# 09_MIPI_LCD_TX1.net
KiCad netlist of a schematic drawn in Altium Designer
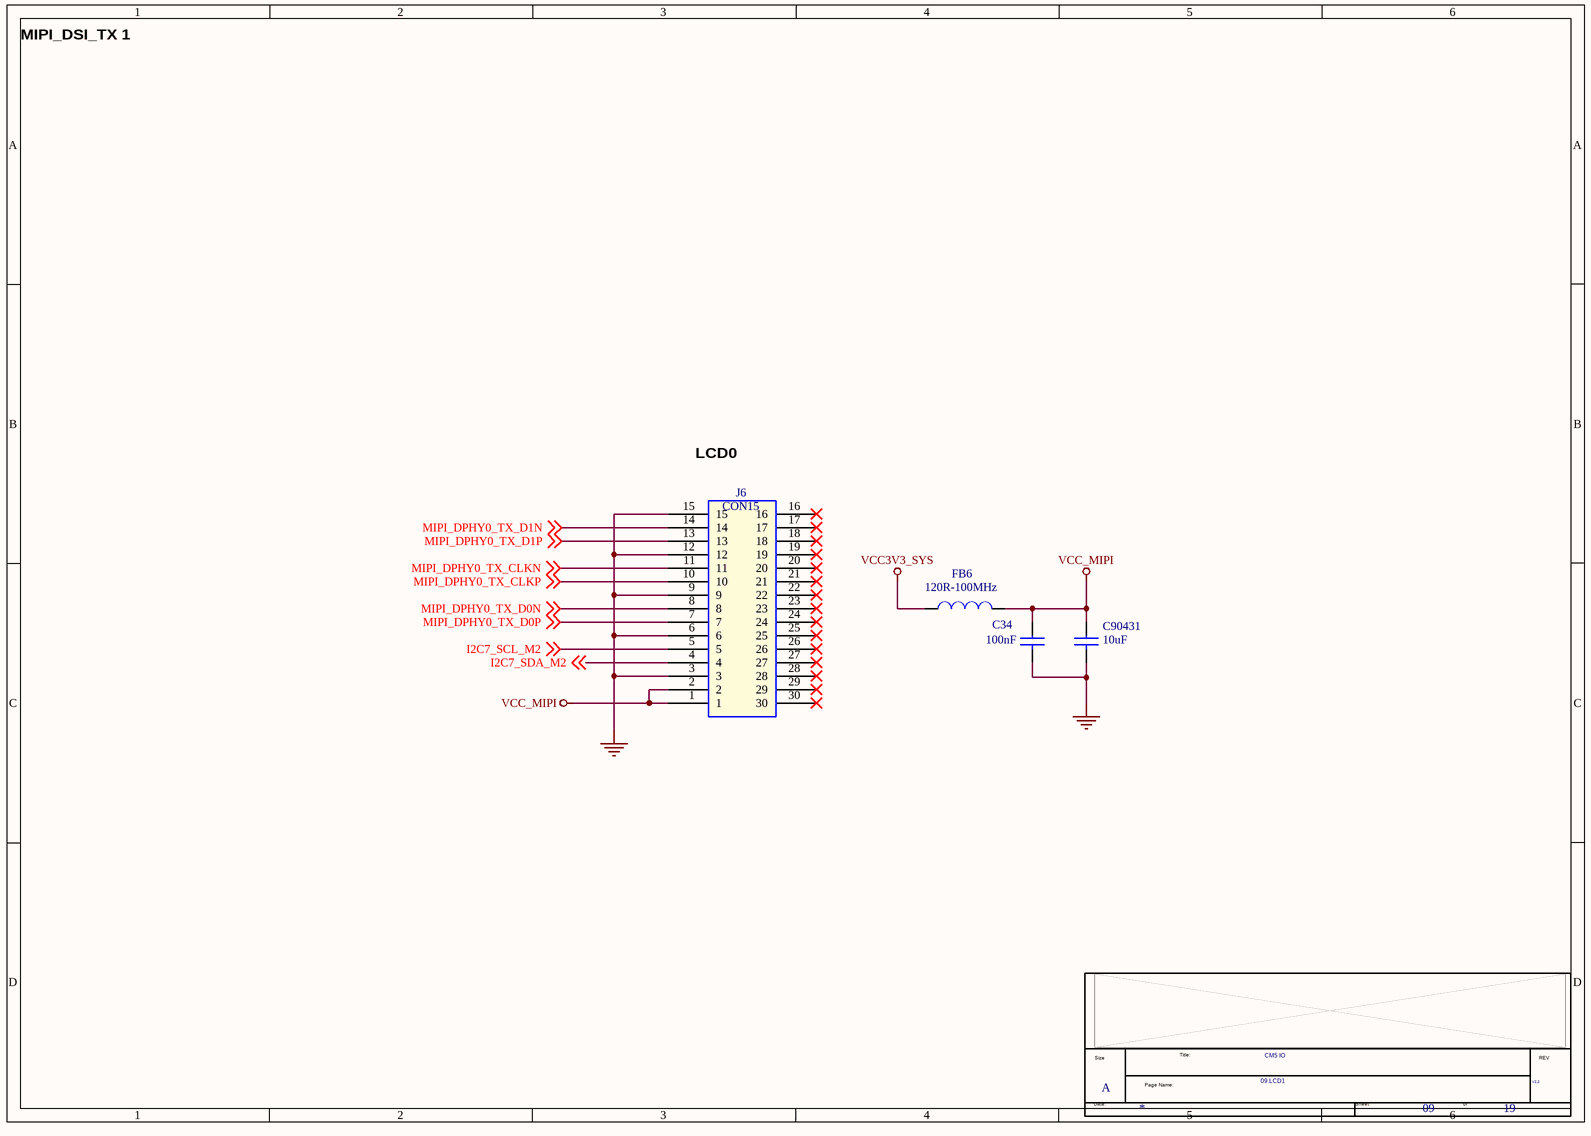
[diagram p0: 09_MIPI_LCD_TX1.SchDoc]

(export (version "E")
  (design (tool "Eeschema 10.0.6"))
  (components
    (comp (ref "*")
      (value "radxa_1010")
      (fields
        (field (name "DOC") "09.LCD1")
        (field (name "REVCODE") "V2.2")
        (field (name "TITLE") "CM5 IO")
        (field (name "PAGE SIZE") "A")
        (field (name "PAGE NUMBER") "09")
        (field (name "PAGE COUNT") "19")
      )
      (libsource (lib "*") (part "radxa_1010"))
    )
    (comp (ref "C34")
      (value "100nF")
      (footprint "C0402")
      (description "cap,100.00nF,+/-10%,16V,X5R,C0402")
      (fields
        (field (name "VOLTAGE") "16V")
        (field (name "MANUFACTURER") "TDK")
        (field (name "CREATED BY") "JJJ")
      )
      (libsource (lib "*") (part "CAP NP_0_Dup4"))
    )
    (comp (ref "C90431")
      (value "10uF")
      (footprint "C0603")
      (description "cap,10.00uF,+/-10%,10V,X5R,C0805")
      (fields
        (field (name "VOLTAGE") "10V")
        (field (name "MANUFACTURER") "TDK")
        (field (name "CREATED BY") "JJJ")
      )
      (libsource (lib "*") (part "CAP NP_0_Dup3"))
    )
    (comp (ref "FB6")
      (value "120R-100MHz")
      (footprint "L0402")
      (description "BEAD,120R@100MHz,current=2000mA,0603")
      (fields
        (field (name "TOLERANCE") "25%")
        (field (name "MANUFACTURER") "Murata")
        (field (name "CREATED BY") "DZS")
      )
      (libsource (lib "*") (part "BEAD_0"))
    )
    (comp (ref "J6") (value "CON15") (footprint "FPC15PIN-1.0MM-LS") (libsource (lib "*") (part "CON15_4")))
  )
  (nets
    (net (code "1") (name "GND") (class "Default")
      (node (ref "C34") (pin "2") (pinfunction "2_2") (pintype "passive"))
      (node (ref "C90431") (pin "2") (pinfunction "2_2") (pintype "passive"))
      (node (ref "J6") (pin "12") (pinfunction "12_12") (pintype "passive"))
      (node (ref "J6") (pin "15") (pinfunction "15_15") (pintype "passive"))
      (node (ref "J6") (pin "3") (pinfunction "3_3") (pintype "passive"))
      (node (ref "J6") (pin "6") (pinfunction "6_6") (pintype "passive"))
      (node (ref "J6") (pin "9") (pinfunction "9_9") (pintype "passive"))
    )
    (net (code "2") (name "I2C7_SCL_M2") (class "Default")
      (node (ref "J6") (pin "5") (pinfunction "5_5") (pintype "passive"))
    )
    (net (code "3") (name "I2C7_SDA_M2") (class "Default")
      (node (ref "J6") (pin "4") (pinfunction "4_4") (pintype "passive"))
    )
    (net (code "4") (name "MIPI_DPHY0_TX_CLKN") (class "Default")
      (node (ref "J6") (pin "11") (pinfunction "11_11") (pintype "passive"))
    )
    (net (code "5") (name "MIPI_DPHY0_TX_CLKP") (class "Default")
      (node (ref "J6") (pin "10") (pinfunction "10_10") (pintype "passive"))
    )
    (net (code "6") (name "MIPI_DPHY0_TX_D0N") (class "Default")
      (node (ref "J6") (pin "8") (pinfunction "8_8") (pintype "passive"))
    )
    (net (code "7") (name "MIPI_DPHY0_TX_D0P") (class "Default")
      (node (ref "J6") (pin "7") (pinfunction "7_7") (pintype "passive"))
    )
    (net (code "8") (name "MIPI_DPHY0_TX_D1N") (class "Default")
      (node (ref "J6") (pin "14") (pinfunction "14_14") (pintype "passive"))
    )
    (net (code "9") (name "MIPI_DPHY0_TX_D1P") (class "Default")
      (node (ref "J6") (pin "13") (pinfunction "13_13") (pintype "passive"))
    )
    (net (code "10") (name "VCC3V3_SYS") (class "Default")
      (node (ref "FB6") (pin "1") (pinfunction "1_1") (pintype "passive"))
    )
    (net (code "11") (name "VCC_MIPI") (class "Default")
      (node (ref "C34") (pin "1") (pinfunction "1_1") (pintype "passive"))
      (node (ref "C90431") (pin "1") (pinfunction "1_1") (pintype "passive"))
      (node (ref "FB6") (pin "2") (pinfunction "2_2") (pintype "passive"))
      (node (ref "J6") (pin "1") (pinfunction "1_1") (pintype "passive"))
      (node (ref "J6") (pin "2") (pinfunction "2_2") (pintype "passive"))
    )
    (net (code "12") (name "unconnected-(J6-Pad16)") (class "Default")
      (node (ref "J6") (pin "16") (pinfunction "16_16") (pintype "passive+no_connect"))
    )
    (net (code "13") (name "unconnected-(J6-Pad17)") (class "Default")
      (node (ref "J6") (pin "17") (pinfunction "17_17") (pintype "passive+no_connect"))
    )
    (net (code "14") (name "unconnected-(J6-Pad18)") (class "Default")
      (node (ref "J6") (pin "18") (pinfunction "18_18") (pintype "passive+no_connect"))
    )
    (net (code "15") (name "unconnected-(J6-Pad19)") (class "Default")
      (node (ref "J6") (pin "19") (pinfunction "19_19") (pintype "passive+no_connect"))
    )
    (net (code "16") (name "unconnected-(J6-Pad20)") (class "Default")
      (node (ref "J6") (pin "20") (pinfunction "20_20") (pintype "passive+no_connect"))
    )
    (net (code "17") (name "unconnected-(J6-Pad21)") (class "Default")
      (node (ref "J6") (pin "21") (pinfunction "21_21") (pintype "passive+no_connect"))
    )
    (net (code "18") (name "unconnected-(J6-Pad22)") (class "Default")
      (node (ref "J6") (pin "22") (pinfunction "22_22") (pintype "passive+no_connect"))
    )
    (net (code "19") (name "unconnected-(J6-Pad23)") (class "Default")
      (node (ref "J6") (pin "23") (pinfunction "23_23") (pintype "passive+no_connect"))
    )
    (net (code "20") (name "unconnected-(J6-Pad24)") (class "Default")
      (node (ref "J6") (pin "24") (pinfunction "24_24") (pintype "passive+no_connect"))
    )
    (net (code "21") (name "unconnected-(J6-Pad25)") (class "Default")
      (node (ref "J6") (pin "25") (pinfunction "25_25") (pintype "passive+no_connect"))
    )
    (net (code "22") (name "unconnected-(J6-Pad26)") (class "Default")
      (node (ref "J6") (pin "26") (pinfunction "26_26") (pintype "passive+no_connect"))
    )
    (net (code "23") (name "unconnected-(J6-Pad27)") (class "Default")
      (node (ref "J6") (pin "27") (pinfunction "27_27") (pintype "passive+no_connect"))
    )
    (net (code "24") (name "unconnected-(J6-Pad28)") (class "Default")
      (node (ref "J6") (pin "28") (pinfunction "28_28") (pintype "passive+no_connect"))
    )
    (net (code "25") (name "unconnected-(J6-Pad29)") (class "Default")
      (node (ref "J6") (pin "29") (pinfunction "29_29") (pintype "passive+no_connect"))
    )
    (net (code "26") (name "unconnected-(J6-Pad30)") (class "Default")
      (node (ref "J6") (pin "30") (pinfunction "30_30") (pintype "passive+no_connect"))
    )
  )
)
